# ECG.net
KiCad netlist of a schematic drawn in EAGLE
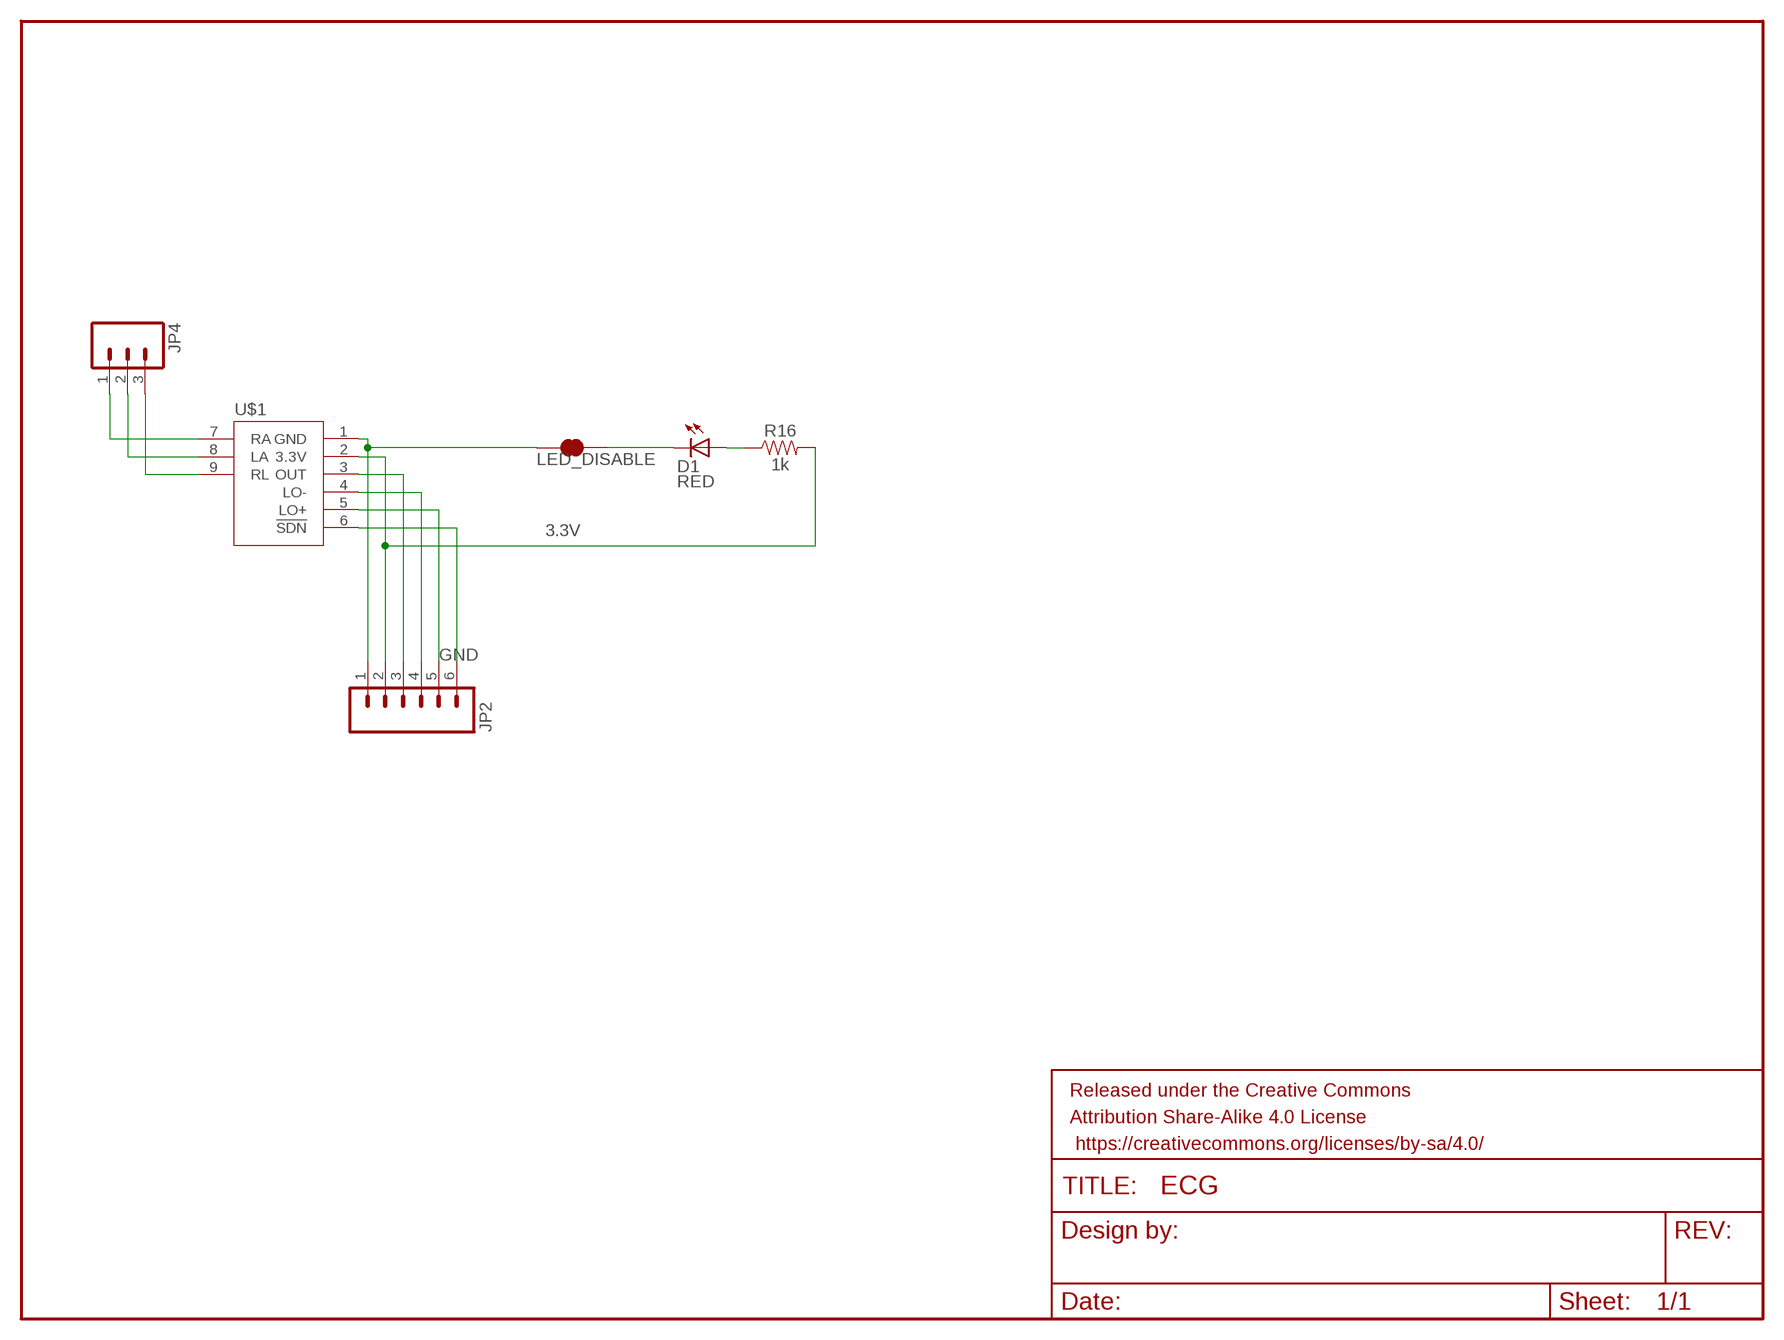
[diagram p0: schematic, sheet 1]

(export (version "E")
  (design (tool "Eeschema 10.0.6"))
  (components
    (comp (ref "D1")
      (value "RED")
      (footprint "eagle-import:LED-0603")
      (libsource (lib "eagle-import") (part "LED-RED0603"))
    )
    (comp (ref "FRAME1")
      (value "FRAME-LETTERNO_PACKAGE")
      (footprint "eagle-import:DUMMY")
      (fields (field (name "DESIGNER") "Nobody"))
      (libsource (lib "eagle-import") (part "FRAME-LETTERNO_PACKAGE"))
    )
    (comp (ref "JP2")
      (value "M06SIP")
      (footprint "eagle-import:1X06")
      (libsource (lib "eagle-import") (part "M06SIP"))
    )
    (comp (ref "JP4")
      (value "M03PTH")
      (footprint "eagle-import:1X03")
      (libsource (lib "eagle-import") (part "M03PTH"))
    )
    (comp (ref "LED_DISABLE")
      (value "JUMPER-SMT_2_NC_TRACE_SILK")
      (footprint "eagle-import:SMT-JUMPER_2_NC_TRACE_SILK")
      (libsource (lib "eagle-import") (part "JUMPER-SMT_2_NC_TRACE_SILK"))
    )
    (comp (ref "R16")
      (value "1k")
      (footprint "eagle-import:0603")
      (libsource (lib "eagle-import") (part "1KOHM-0603-1/10W-1%"))
    )
    (comp (ref "U$1")
      (value "SPARK_ECG")
      (footprint "eagle-import:SPARK_ECG")
      (libsource (lib "eagle-import") (part "SPARK_ECG"))
    )
  )
  (nets
    (net (code "1") (name "/3.3V") (class "Default")
      (node (ref "JP2") (pin "2") (pinfunction "2_2") (pintype "passive"))
      (node (ref "R16") (pin "2") (pinfunction "2_2") (pintype "passive"))
      (node (ref "U$1") (pin "2") (pinfunction "3.3V_2") (pintype "power_in"))
    )
    (net (code "2") (name "/GND") (class "Default")
      (node (ref "JP2") (pin "1") (pinfunction "1_1") (pintype "passive"))
      (node (ref "LED_DISABLE") (pin "1") (pinfunction "1_1") (pintype "passive"))
      (node (ref "U$1") (pin "1") (pinfunction "GND_1") (pintype "power_in"))
    )
    (net (code "3") (name "Net-(D1-PadA)") (class "Default")
      (node (ref "D1") (pin "A") (pinfunction "A_A") (pintype "passive"))
      (node (ref "R16") (pin "1") (pinfunction "1_1") (pintype "passive"))
    )
    (net (code "4") (name "Net-(D1-PadC)") (class "Default")
      (node (ref "D1") (pin "C") (pinfunction "C_C") (pintype "passive"))
      (node (ref "LED_DISABLE") (pin "2") (pinfunction "2_2") (pintype "passive"))
    )
    (net (code "5") (name "Net-(U$1-LA)") (class "Default")
      (node (ref "JP4") (pin "2") (pinfunction "2_2") (pintype "passive"))
      (node (ref "U$1") (pin "8") (pinfunction "LA_8") (pintype "input"))
    )
    (net (code "6") (name "Net-(U$1-LO+)") (class "Default")
      (node (ref "JP2") (pin "5") (pinfunction "5_5") (pintype "passive"))
      (node (ref "U$1") (pin "5") (pinfunction "LO+_5") (pintype "output"))
    )
    (net (code "7") (name "Net-(U$1-LO-)") (class "Default")
      (node (ref "JP2") (pin "4") (pinfunction "4_4") (pintype "passive"))
      (node (ref "U$1") (pin "4") (pinfunction "LO-_4") (pintype "output"))
    )
    (net (code "8") (name "Net-(U$1-OUT)") (class "Default")
      (node (ref "JP2") (pin "3") (pinfunction "3_3") (pintype "passive"))
      (node (ref "U$1") (pin "3") (pinfunction "OUT_3") (pintype "output"))
    )
    (net (code "9") (name "Net-(U$1-RA)") (class "Default")
      (node (ref "JP4") (pin "1") (pinfunction "1_1") (pintype "passive"))
      (node (ref "U$1") (pin "7") (pinfunction "RA_7") (pintype "input"))
    )
    (net (code "10") (name "Net-(U$1-RL)") (class "Default")
      (node (ref "JP4") (pin "3") (pinfunction "3_3") (pintype "passive"))
      (node (ref "U$1") (pin "9") (pinfunction "RL_9") (pintype "input"))
    )
    (net (code "11") (name "Net-(U$1-~{SDN})") (class "Default")
      (node (ref "JP2") (pin "6") (pinfunction "6_6") (pintype "passive"))
      (node (ref "U$1") (pin "6") (pinfunction "~{SDN}_6") (pintype "bidirectional"))
    )
  )
)
